# RAK811_Reference_design.net
KiCad netlist of a schematic drawn in Altium Designer
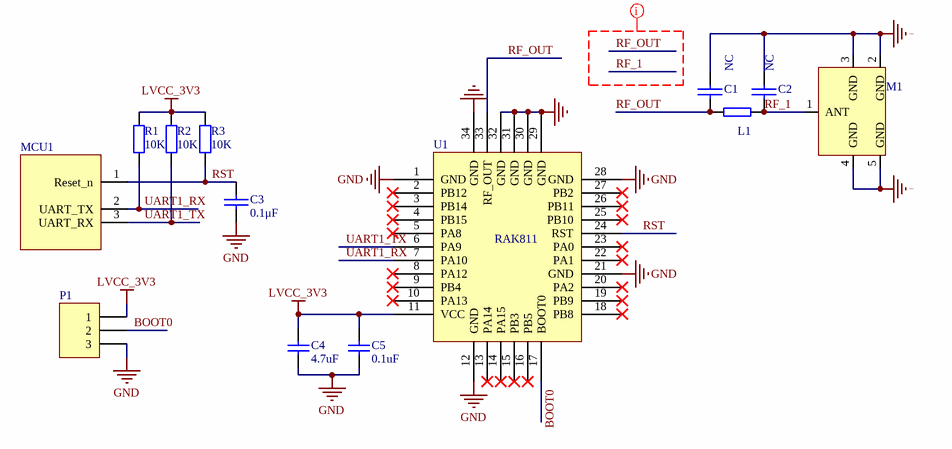
[diagram p0: RAK811 Reference design.SchDoc]

(export (version "E")
  (design (tool "Eeschema 10.0.6"))
  (components
    (comp (ref "C1")
      (value "NC")
      (footprint "0603AC")
      (description "Capacitor")
      (libsource (lib "电阻容感类") (part "CAP"))
    )
    (comp (ref "C2")
      (value "NC")
      (footprint "0603AC")
      (description "Capacitor")
      (libsource (lib "电阻容感类") (part "CAP"))
    )
    (comp (ref "C3")
      (value "0.1μF")
      (footprint "0603AC")
      (description "Capacitor")
      (libsource (lib "电阻容感类") (part "CAP"))
    )
    (comp (ref "C4")
      (value "4.7uF")
      (footprint "0603AC")
      (description "Capacitor")
      (fields (field (name "Comment") "Cap") (field (name "PUBLISHER") "Altium Limited"))
      (libsource (lib "Miscellaneous Devices") (part "Cap"))
    )
    (comp (ref "C5")
      (value "0.1uF")
      (footprint "0603AC")
      (description "Capacitor")
      (fields (field (name "Comment") "Cap") (field (name "PUBLISHER") "Altium Limited"))
      (libsource (lib "Miscellaneous Devices") (part "Cap"))
    )
    (comp (ref "L1") (value "~") (footprint "0603AR") (libsource (lib "电阻容感类") (part "RES")))
    (comp (ref "M1") (value "MCX-KWE") (footprint "SMA-KWE天线底座") (libsource (lib "接口类") (part "MCX-KWE")))
    (comp (ref "MCU1")
      (value "MCU")
      (footprint "HDR1X2")
      (description "Header, 2-Pin")
      (fields (field (name "PUBLISHER") "Altium Limited"))
      (libsource (lib "LORA") (part "MCU"))
    )
    (comp (ref "P1")
      (value "~")
      (footprint "HDR1X3")
      (description "Header, 3-Pin")
      (fields (field (name "PUBLISHER") "Altium Limited"))
      (libsource (lib "Miscellaneous Connectors") (part "Header 3"))
    )
    (comp (ref "R1")
      (value "10K")
      (footprint "0603AR")
      (description "Resistor")
      (fields (field (name "PUBLISHER") "Altium Limited"))
      (libsource (lib "*") (part "Res2"))
    )
    (comp (ref "R2")
      (value "10K")
      (footprint "0603AR")
      (description "Resistor")
      (fields (field (name "PUBLISHER") "Altium Limited"))
      (libsource (lib "*") (part "Res2"))
    )
    (comp (ref "R3")
      (value "10K")
      (footprint "0603AR")
      (description "Resistor")
      (fields (field (name "PUBLISHER") "Altium Limited"))
      (libsource (lib "*") (part "Res2"))
    )
    (comp (ref "U1") (value "RAK811") (footprint "LORA") (libsource (lib "Schlib1") (part "LORA Model")))
  )
  (nets
    (net (code "1") (name "/BOOT0") (class "Default")
      (node (ref "P1") (pin "2") (pinfunction "2_2") (pintype "passive"))
      (node (ref "U1") (pin "17") (pinfunction "BOOT0_17") (pintype "passive"))
    )
    (net (code "2") (name "/RF_1") (class "Default")
      (node (ref "C2") (pin "2") (pinfunction "2_2") (pintype "passive"))
      (node (ref "L1") (pin "2") (pinfunction "2_2") (pintype "passive"))
      (node (ref "M1") (pin "1") (pinfunction "ANT_1") (pintype "passive"))
    )
    (net (code "4") (name "/RST") (class "Default")
      (node (ref "C3") (pin "2") (pinfunction "2_2") (pintype "passive"))
      (node (ref "MCU1") (pin "1") (pinfunction "Reset_n_1") (pintype "passive"))
      (node (ref "R3") (pin "1") (pinfunction "1_1") (pintype "passive"))
      (node (ref "U1") (pin "24") (pinfunction "RST_24") (pintype "passive"))
    )
    (net (code "5") (name "/UART1_RX") (class "Default")
      (node (ref "MCU1") (pin "2") (pinfunction "UART_TX_2") (pintype "passive"))
      (node (ref "R1") (pin "1") (pinfunction "1_1") (pintype "passive"))
      (node (ref "U1") (pin "7") (pinfunction "PA10_7") (pintype "passive"))
    )
    (net (code "6") (name "/UART1_TX") (class "Default")
      (node (ref "MCU1") (pin "3") (pinfunction "UART_RX_3") (pintype "passive"))
      (node (ref "R2") (pin "1") (pinfunction "1_1") (pintype "passive"))
      (node (ref "U1") (pin "6") (pinfunction "PA9_6") (pintype "passive"))
    )
    (net (code "7") (name "/{RF_OUT}") (class "Default")
      (node (ref "C1") (pin "2") (pinfunction "2_2") (pintype "passive"))
      (node (ref "L1") (pin "1") (pinfunction "1_1") (pintype "passive"))
      (node (ref "U1") (pin "33") (pinfunction "RF_OUT_33") (pintype "passive"))
    )
    (net (code "8") (name "GND") (class "Default")
      (node (ref "C1") (pin "1") (pinfunction "1_1") (pintype "passive"))
      (node (ref "C2") (pin "1") (pinfunction "1_1") (pintype "passive"))
      (node (ref "C3") (pin "1") (pinfunction "1_1") (pintype "passive"))
      (node (ref "C4") (pin "1") (pinfunction "1_1") (pintype "passive"))
      (node (ref "C5") (pin "1") (pinfunction "1_1") (pintype "passive"))
      (node (ref "M1") (pin "2") (pinfunction "GND_2") (pintype "passive"))
      (node (ref "M1") (pin "3") (pinfunction "GND_3") (pintype "passive"))
      (node (ref "M1") (pin "4") (pinfunction "GND_4") (pintype "passive"))
      (node (ref "M1") (pin "5") (pinfunction "GND_5") (pintype "passive"))
      (node (ref "P1") (pin "3") (pinfunction "3_3") (pintype "passive"))
      (node (ref "U1") (pin "1") (pinfunction "GND_1") (pintype "passive"))
      (node (ref "U1") (pin "12") (pinfunction "GND_12") (pintype "passive"))
      (node (ref "U1") (pin "21") (pinfunction "GND_21") (pintype "passive"))
      (node (ref "U1") (pin "28") (pinfunction "GND_28") (pintype "passive"))
      (node (ref "U1") (pin "29") (pinfunction "GND_29") (pintype "passive"))
      (node (ref "U1") (pin "30") (pinfunction "GND_30") (pintype "passive"))
      (node (ref "U1") (pin "31") (pinfunction "GND_31") (pintype "passive"))
      (node (ref "U1") (pin "32") (pinfunction "GND_32") (pintype "passive"))
      (node (ref "U1") (pin "34") (pinfunction "GND_34") (pintype "passive"))
    )
    (net (code "9") (name "LVCC_3V3") (class "Default")
      (node (ref "C4") (pin "2") (pinfunction "2_2") (pintype "passive"))
      (node (ref "C5") (pin "2") (pinfunction "2_2") (pintype "passive"))
      (node (ref "P1") (pin "1") (pinfunction "1_1") (pintype "passive"))
      (node (ref "R1") (pin "2") (pinfunction "2_2") (pintype "passive"))
      (node (ref "R2") (pin "2") (pinfunction "2_2") (pintype "passive"))
      (node (ref "R3") (pin "2") (pinfunction "2_2") (pintype "passive"))
      (node (ref "U1") (pin "11") (pinfunction "VCC_11") (pintype "passive"))
    )
    (net (code "10") (name "unconnected-(U1-PA0-Pad23)") (class "Default")
      (node (ref "U1") (pin "23") (pinfunction "PA0_23") (pintype "passive+no_connect"))
    )
    (net (code "11") (name "unconnected-(U1-PA1-Pad22)") (class "Default")
      (node (ref "U1") (pin "22") (pinfunction "PA1_22") (pintype "passive+no_connect"))
    )
    (net (code "12") (name "unconnected-(U1-PA2-Pad20)") (class "Default")
      (node (ref "U1") (pin "20") (pinfunction "PA2_20") (pintype "passive+no_connect"))
    )
    (net (code "13") (name "unconnected-(U1-PA8-Pad5)") (class "Default")
      (node (ref "U1") (pin "5") (pinfunction "PA8_5") (pintype "passive+no_connect"))
    )
    (net (code "14") (name "unconnected-(U1-PA12-Pad8)") (class "Default")
      (node (ref "U1") (pin "8") (pinfunction "PA12_8") (pintype "passive+no_connect"))
    )
    (net (code "15") (name "unconnected-(U1-PA13-Pad10)") (class "Default")
      (node (ref "U1") (pin "10") (pinfunction "PA13_10") (pintype "passive+no_connect"))
    )
    (net (code "16") (name "unconnected-(U1-PA14-Pad13)") (class "Default")
      (node (ref "U1") (pin "13") (pinfunction "PA14_13") (pintype "passive+no_connect"))
    )
    (net (code "17") (name "unconnected-(U1-PA15-Pad14)") (class "Default")
      (node (ref "U1") (pin "14") (pinfunction "PA15_14") (pintype "passive+no_connect"))
    )
    (net (code "18") (name "unconnected-(U1-PB2-Pad27)") (class "Default")
      (node (ref "U1") (pin "27") (pinfunction "PB2_27") (pintype "passive+no_connect"))
    )
    (net (code "19") (name "unconnected-(U1-PB3-Pad15)") (class "Default")
      (node (ref "U1") (pin "15") (pinfunction "PB3_15") (pintype "passive+no_connect"))
    )
    (net (code "20") (name "unconnected-(U1-PB4-Pad9)") (class "Default")
      (node (ref "U1") (pin "9") (pinfunction "PB4_9") (pintype "passive+no_connect"))
    )
    (net (code "21") (name "unconnected-(U1-PB5-Pad16)") (class "Default")
      (node (ref "U1") (pin "16") (pinfunction "PB5_16") (pintype "passive+no_connect"))
    )
    (net (code "22") (name "unconnected-(U1-PB8-Pad18)") (class "Default")
      (node (ref "U1") (pin "18") (pinfunction "PB8_18") (pintype "passive+no_connect"))
    )
    (net (code "23") (name "unconnected-(U1-PB9-Pad19)") (class "Default")
      (node (ref "U1") (pin "19") (pinfunction "PB9_19") (pintype "passive+no_connect"))
    )
    (net (code "24") (name "unconnected-(U1-PB10-Pad25)") (class "Default")
      (node (ref "U1") (pin "25") (pinfunction "PB10_25") (pintype "passive+no_connect"))
    )
    (net (code "25") (name "unconnected-(U1-PB11-Pad26)") (class "Default")
      (node (ref "U1") (pin "26") (pinfunction "PB11_26") (pintype "passive+no_connect"))
    )
    (net (code "26") (name "unconnected-(U1-PB12-Pad2)") (class "Default")
      (node (ref "U1") (pin "2") (pinfunction "PB12_2") (pintype "passive+no_connect"))
    )
    (net (code "27") (name "unconnected-(U1-PB14-Pad3)") (class "Default")
      (node (ref "U1") (pin "3") (pinfunction "PB14_3") (pintype "passive+no_connect"))
    )
    (net (code "28") (name "unconnected-(U1-PB15-Pad4)") (class "Default")
      (node (ref "U1") (pin "4") (pinfunction "PB15_4") (pintype "passive+no_connect"))
    )
  )
)
